# led-monitoring-SN74HC365PW.net
KiCad netlist of a schematic drawn in Altium Designer
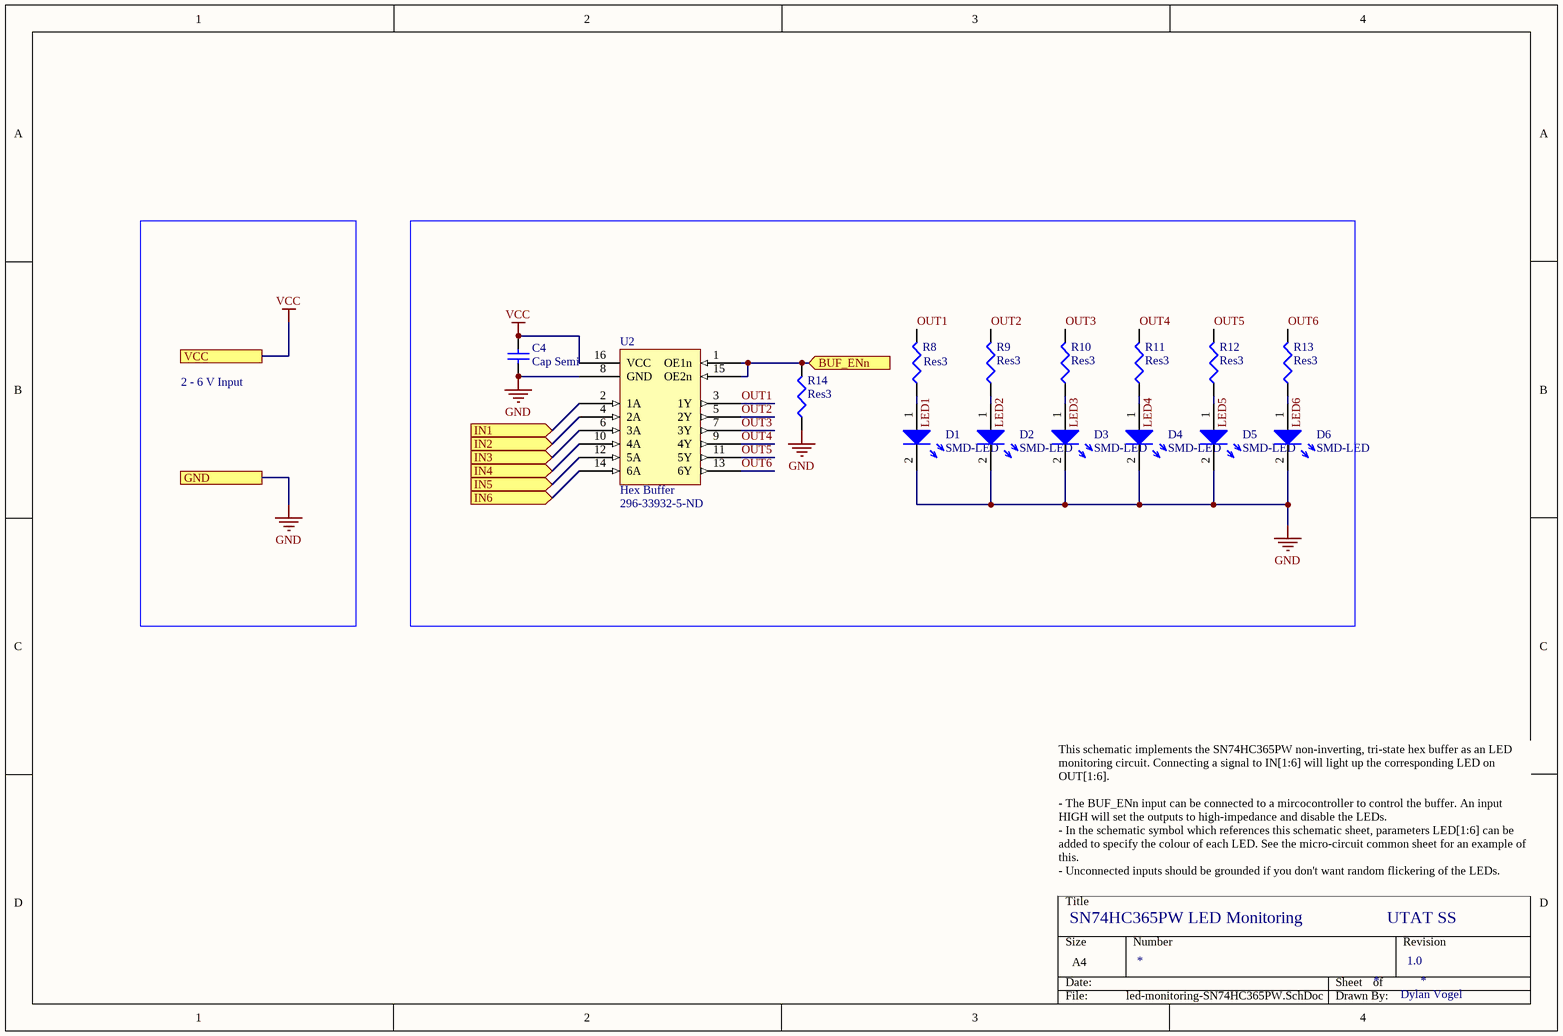
[diagram p0: led-monitoring-SN74HC365PW.SchDoc]

(export (version "E")
  (design (tool "Eeschema 10.0.6"))
  (components
    (comp (ref "C4")
      (value "Cap Semi")
      (footprint "C1206")
      (description "Capacitor (Semiconductor SIM Model)")
      (fields (field (name "PUBLISHER") "Altium Limited"))
      (libsource (lib "Miscellaneous Devices") (part "Cap Semi"))
    )
    (comp (ref "D1")
      (value "SMD-LED")
      (footprint "0603-LED")
      (description "Just a generic LED")
      (libsource (lib "heron-general") (part "LED"))
    )
    (comp (ref "D2")
      (value "SMD-LED")
      (footprint "0603-LED")
      (description "Just a generic LED")
      (libsource (lib "heron-general") (part "LED"))
    )
    (comp (ref "D3")
      (value "SMD-LED")
      (footprint "0603-LED")
      (description "Just a generic LED")
      (libsource (lib "heron-general") (part "LED"))
    )
    (comp (ref "D4")
      (value "SMD-LED")
      (footprint "0603-LED")
      (description "Just a generic LED")
      (libsource (lib "heron-general") (part "LED"))
    )
    (comp (ref "D5")
      (value "SMD-LED")
      (footprint "0603-LED")
      (description "Just a generic LED")
      (libsource (lib "heron-general") (part "LED"))
    )
    (comp (ref "D6")
      (value "SMD-LED")
      (footprint "0603-LED")
      (description "Just a generic LED")
      (libsource (lib "heron-general") (part "LED"))
    )
    (comp (ref "R8")
      (value "Res3")
      (footprint "J1-0603")
      (description "Resistor")
      (fields (field (name "PUBLISHER") "Altium Limited"))
      (libsource (lib "Miscellaneous Devices") (part "Res3"))
    )
    (comp (ref "R9")
      (value "Res3")
      (footprint "J1-0603")
      (description "Resistor")
      (fields (field (name "PUBLISHER") "Altium Limited"))
      (libsource (lib "Miscellaneous Devices") (part "Res3"))
    )
    (comp (ref "R10")
      (value "Res3")
      (footprint "J1-0603")
      (description "Resistor")
      (fields (field (name "PUBLISHER") "Altium Limited"))
      (libsource (lib "Miscellaneous Devices") (part "Res3"))
    )
    (comp (ref "R11")
      (value "Res3")
      (footprint "J1-0603")
      (description "Resistor")
      (fields (field (name "PUBLISHER") "Altium Limited"))
      (libsource (lib "Miscellaneous Devices") (part "Res3"))
    )
    (comp (ref "R12")
      (value "Res3")
      (footprint "J1-0603")
      (description "Resistor")
      (fields (field (name "PUBLISHER") "Altium Limited"))
      (libsource (lib "Miscellaneous Devices") (part "Res3"))
    )
    (comp (ref "R13")
      (value "Res3")
      (footprint "J1-0603")
      (description "Resistor")
      (fields (field (name "PUBLISHER") "Altium Limited"))
      (libsource (lib "Miscellaneous Devices") (part "Res3"))
    )
    (comp (ref "R14")
      (value "Res3")
      (footprint "J1-0603")
      (description "Resistor")
      (fields (field (name "PUBLISHER") "Altium Limited"))
      (libsource (lib "Miscellaneous Devices") (part "Res3"))
    )
    (comp (ref "U2")
      (value "Hex Buffer")
      (footprint "SOP65P640X120-16N")
      (description "Hex non-inverting buffer with 3-state outputs")
      (fields (field (name "SUPPLIER PART NUMBER 1") "296-33932-5-ND"))
      (libsource (lib "heron-general") (part "SN74HC365PW"))
    )
  )
  (nets
    (net (code "1") (name "/BUF_ENn") (class "Default")
      (node (ref "R14") (pin "2") (pinfunction "2_2") (pintype "passive"))
      (node (ref "U2") (pin "1") (pinfunction "OE1n_1") (pintype "input"))
      (node (ref "U2") (pin "15") (pinfunction "OE2n_15") (pintype "input"))
    )
    (net (code "2") (name "/IN1") (class "Default")
      (node (ref "U2") (pin "2") (pinfunction "1A_2") (pintype "input"))
    )
    (net (code "3") (name "/IN2") (class "Default")
      (node (ref "U2") (pin "4") (pinfunction "2A_4") (pintype "input"))
    )
    (net (code "4") (name "/IN3") (class "Default")
      (node (ref "U2") (pin "6") (pinfunction "3A_6") (pintype "input"))
    )
    (net (code "5") (name "/IN4") (class "Default")
      (node (ref "U2") (pin "10") (pinfunction "4A_10") (pintype "input"))
    )
    (net (code "6") (name "/IN5") (class "Default")
      (node (ref "U2") (pin "12") (pinfunction "5A_12") (pintype "input"))
    )
    (net (code "7") (name "/IN6") (class "Default")
      (node (ref "U2") (pin "14") (pinfunction "6A_14") (pintype "input"))
    )
    (net (code "8") (name "/LED1") (class "Default")
      (node (ref "D1") (pin "1") (pinfunction "1_1") (pintype "passive"))
      (node (ref "R8") (pin "1") (pinfunction "1_1") (pintype "passive"))
    )
    (net (code "9") (name "/LED2") (class "Default")
      (node (ref "D2") (pin "1") (pinfunction "1_1") (pintype "passive"))
      (node (ref "R9") (pin "1") (pinfunction "1_1") (pintype "passive"))
    )
    (net (code "10") (name "/LED3") (class "Default")
      (node (ref "D3") (pin "1") (pinfunction "1_1") (pintype "passive"))
      (node (ref "R10") (pin "1") (pinfunction "1_1") (pintype "passive"))
    )
    (net (code "11") (name "/LED4") (class "Default")
      (node (ref "D4") (pin "1") (pinfunction "1_1") (pintype "passive"))
      (node (ref "R11") (pin "1") (pinfunction "1_1") (pintype "passive"))
    )
    (net (code "12") (name "/LED5") (class "Default")
      (node (ref "D5") (pin "1") (pinfunction "1_1") (pintype "passive"))
      (node (ref "R12") (pin "1") (pinfunction "1_1") (pintype "passive"))
    )
    (net (code "13") (name "/LED6") (class "Default")
      (node (ref "D6") (pin "1") (pinfunction "1_1") (pintype "passive"))
      (node (ref "R13") (pin "1") (pinfunction "1_1") (pintype "passive"))
    )
    (net (code "14") (name "/OUT1") (class "Default")
      (node (ref "R8") (pin "2") (pinfunction "2_2") (pintype "passive"))
      (node (ref "U2") (pin "3") (pinfunction "1Y_3") (pintype "output"))
    )
    (net (code "15") (name "/OUT2") (class "Default")
      (node (ref "R9") (pin "2") (pinfunction "2_2") (pintype "passive"))
      (node (ref "U2") (pin "5") (pinfunction "2Y_5") (pintype "output"))
    )
    (net (code "16") (name "/OUT3") (class "Default")
      (node (ref "R10") (pin "2") (pinfunction "2_2") (pintype "passive"))
      (node (ref "U2") (pin "7") (pinfunction "3Y_7") (pintype "output"))
    )
    (net (code "17") (name "/OUT4") (class "Default")
      (node (ref "R11") (pin "2") (pinfunction "2_2") (pintype "passive"))
      (node (ref "U2") (pin "9") (pinfunction "4Y_9") (pintype "output"))
    )
    (net (code "18") (name "/OUT5") (class "Default")
      (node (ref "R12") (pin "2") (pinfunction "2_2") (pintype "passive"))
      (node (ref "U2") (pin "11") (pinfunction "5Y_11") (pintype "output"))
    )
    (net (code "19") (name "/OUT6") (class "Default")
      (node (ref "R13") (pin "2") (pinfunction "2_2") (pintype "passive"))
      (node (ref "U2") (pin "13") (pinfunction "6Y_13") (pintype "output"))
    )
    (net (code "20") (name "GND") (class "Default")
      (node (ref "C4") (pin "1") (pinfunction "1_1") (pintype "passive"))
      (node (ref "D1") (pin "2") (pinfunction "2_2") (pintype "passive"))
      (node (ref "D2") (pin "2") (pinfunction "2_2") (pintype "passive"))
      (node (ref "D3") (pin "2") (pinfunction "2_2") (pintype "passive"))
      (node (ref "D4") (pin "2") (pinfunction "2_2") (pintype "passive"))
      (node (ref "D5") (pin "2") (pinfunction "2_2") (pintype "passive"))
      (node (ref "D6") (pin "2") (pinfunction "2_2") (pintype "passive"))
      (node (ref "R14") (pin "1") (pinfunction "1_1") (pintype "passive"))
      (node (ref "U2") (pin "8") (pinfunction "GND_8") (pintype "power_in"))
    )
    (net (code "21") (name "VCC") (class "Default")
      (node (ref "C4") (pin "2") (pinfunction "2_2") (pintype "passive"))
      (node (ref "U2") (pin "16") (pinfunction "VCC_16") (pintype "power_in"))
    )
  )
)
